# Submarine.net
KiCad netlist of a schematic drawn in EAGLE
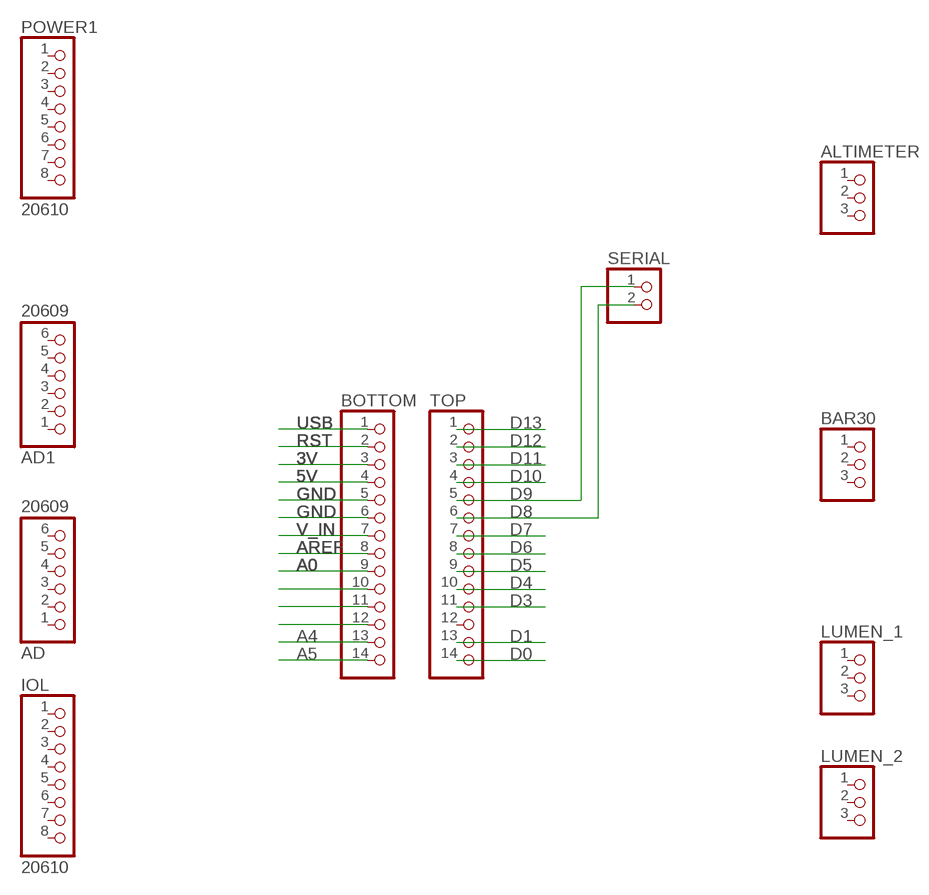
[diagram p0: schematic, sheet 1]

(export (version "E")
  (design (tool "Eeschema 10.0.6"))
  (components
    (comp (ref "AD")
      (value "20609")
      (footprint "eagle-import:1X06_ROUND")
      (libsource (lib "eagle-import") (part "HEADER-1X6ROUND"))
    )
    (comp (ref "AD1")
      (value "20609")
      (footprint "eagle-import:1X06_ROUND")
      (libsource (lib "eagle-import") (part "HEADER-1X6ROUND"))
    )
    (comp (ref "ALTIMETER")
      (value "PINHD-1X3")
      (footprint "eagle-import:1X03")
      (libsource (lib "eagle-import") (part "PINHD-1X3"))
    )
    (comp (ref "BAR30")
      (value "PINHD-1X3")
      (footprint "eagle-import:1X03")
      (libsource (lib "eagle-import") (part "PINHD-1X3"))
    )
    (comp (ref "BOTTOM")
      (value "PINHD-1X14")
      (footprint "eagle-import:1X14")
      (libsource (lib "eagle-import") (part "PINHD-1X14"))
    )
    (comp (ref "IOL")
      (value "20610")
      (footprint "eagle-import:1X08_ROUND")
      (libsource (lib "eagle-import") (part "HEADER-1X8ROUND"))
    )
    (comp (ref "LUMEN_1")
      (value "PINHD-1X3")
      (footprint "eagle-import:1X03")
      (libsource (lib "eagle-import") (part "PINHD-1X3"))
    )
    (comp (ref "LUMEN_2")
      (value "PINHD-1X3")
      (footprint "eagle-import:1X03")
      (libsource (lib "eagle-import") (part "PINHD-1X3"))
    )
    (comp (ref "POWER1")
      (value "20610")
      (footprint "eagle-import:1X08_ROUND_70")
      (libsource (lib "eagle-import") (part "HEADER-1X870MIL"))
    )
    (comp (ref "SERIAL")
      (value "PINHD-1X2")
      (footprint "eagle-import:1X02")
      (libsource (lib "eagle-import") (part "PINHD-1X2"))
    )
    (comp (ref "TOP")
      (value "PINHD-1X14")
      (footprint "eagle-import:1X14")
      (libsource (lib "eagle-import") (part "PINHD-1X14"))
    )
  )
  (nets
    (net (code "1") (name "/3V") (class "Default")
      (node (ref "BOTTOM") (pin "3") (pinfunction "3_3") (pintype "passive"))
    )
    (net (code "2") (name "/5V") (class "Default")
      (node (ref "BOTTOM") (pin "4") (pinfunction "4_4") (pintype "passive"))
    )
    (net (code "3") (name "/A0") (class "Default")
      (node (ref "BOTTOM") (pin "9") (pinfunction "9_9") (pintype "passive"))
    )
    (net (code "4") (name "/A4") (class "Default")
      (node (ref "BOTTOM") (pin "13") (pinfunction "13_13") (pintype "passive"))
    )
    (net (code "5") (name "/A5") (class "Default")
      (node (ref "BOTTOM") (pin "14") (pinfunction "14_14") (pintype "passive"))
    )
    (net (code "6") (name "/AREF") (class "Default")
      (node (ref "BOTTOM") (pin "8") (pinfunction "8_8") (pintype "passive"))
    )
    (net (code "7") (name "/D0") (class "Default")
      (node (ref "TOP") (pin "14") (pinfunction "14_14") (pintype "passive"))
    )
    (net (code "8") (name "/D1") (class "Default")
      (node (ref "TOP") (pin "13") (pinfunction "13_13") (pintype "passive"))
    )
    (net (code "9") (name "/D3") (class "Default")
      (node (ref "TOP") (pin "11") (pinfunction "11_11") (pintype "passive"))
    )
    (net (code "10") (name "/D4") (class "Default")
      (node (ref "TOP") (pin "10") (pinfunction "10_10") (pintype "passive"))
    )
    (net (code "11") (name "/D5") (class "Default")
      (node (ref "TOP") (pin "9") (pinfunction "9_9") (pintype "passive"))
    )
    (net (code "12") (name "/D6") (class "Default")
      (node (ref "TOP") (pin "8") (pinfunction "8_8") (pintype "passive"))
    )
    (net (code "13") (name "/D7") (class "Default")
      (node (ref "TOP") (pin "7") (pinfunction "7_7") (pintype "passive"))
    )
    (net (code "14") (name "/D8") (class "Default")
      (node (ref "SERIAL") (pin "2") (pinfunction "2_2") (pintype "passive"))
      (node (ref "TOP") (pin "6") (pinfunction "6_6") (pintype "passive"))
    )
    (net (code "15") (name "/D9") (class "Default")
      (node (ref "SERIAL") (pin "1") (pinfunction "1_1") (pintype "passive"))
      (node (ref "TOP") (pin "5") (pinfunction "5_5") (pintype "passive"))
    )
    (net (code "16") (name "/D10") (class "Default")
      (node (ref "TOP") (pin "4") (pinfunction "4_4") (pintype "passive"))
    )
    (net (code "17") (name "/D11") (class "Default")
      (node (ref "TOP") (pin "3") (pinfunction "3_3") (pintype "passive"))
    )
    (net (code "18") (name "/D12") (class "Default")
      (node (ref "TOP") (pin "2") (pinfunction "2_2") (pintype "passive"))
    )
    (net (code "19") (name "/D13") (class "Default")
      (node (ref "TOP") (pin "1") (pinfunction "1_1") (pintype "passive"))
    )
    (net (code "20") (name "/GND") (class "Default")
      (node (ref "BOTTOM") (pin "5") (pinfunction "5_5") (pintype "passive"))
      (node (ref "BOTTOM") (pin "6") (pinfunction "6_6") (pintype "passive"))
    )
    (net (code "21") (name "/RST") (class "Default")
      (node (ref "BOTTOM") (pin "2") (pinfunction "2_2") (pintype "passive"))
    )
    (net (code "22") (name "/USB") (class "Default")
      (node (ref "BOTTOM") (pin "1") (pinfunction "1_1") (pintype "passive"))
    )
    (net (code "23") (name "/V_IN") (class "Default")
      (node (ref "BOTTOM") (pin "7") (pinfunction "7_7") (pintype "passive"))
    )
    (net (code "24") (name "unconnected-(AD-Pad1)") (class "Default")
      (node (ref "AD") (pin "1") (pinfunction "1_1") (pintype "passive"))
    )
    (net (code "25") (name "unconnected-(AD-Pad2)") (class "Default")
      (node (ref "AD") (pin "2") (pinfunction "2_2") (pintype "passive"))
    )
    (net (code "26") (name "unconnected-(AD-Pad3)") (class "Default")
      (node (ref "AD") (pin "3") (pinfunction "3_3") (pintype "passive"))
    )
    (net (code "27") (name "unconnected-(AD-Pad4)") (class "Default")
      (node (ref "AD") (pin "4") (pinfunction "4_4") (pintype "passive"))
    )
    (net (code "28") (name "unconnected-(AD-Pad5)") (class "Default")
      (node (ref "AD") (pin "5") (pinfunction "5_5") (pintype "passive"))
    )
    (net (code "29") (name "unconnected-(AD-Pad6)") (class "Default")
      (node (ref "AD") (pin "6") (pinfunction "6_6") (pintype "passive"))
    )
    (net (code "30") (name "unconnected-(AD1-Pad1)") (class "Default")
      (node (ref "AD1") (pin "1") (pinfunction "1_1") (pintype "passive"))
    )
    (net (code "31") (name "unconnected-(AD1-Pad2)") (class "Default")
      (node (ref "AD1") (pin "2") (pinfunction "2_2") (pintype "passive"))
    )
    (net (code "32") (name "unconnected-(AD1-Pad3)") (class "Default")
      (node (ref "AD1") (pin "3") (pinfunction "3_3") (pintype "passive"))
    )
    (net (code "33") (name "unconnected-(AD1-Pad4)") (class "Default")
      (node (ref "AD1") (pin "4") (pinfunction "4_4") (pintype "passive"))
    )
    (net (code "34") (name "unconnected-(AD1-Pad5)") (class "Default")
      (node (ref "AD1") (pin "5") (pinfunction "5_5") (pintype "passive"))
    )
    (net (code "35") (name "unconnected-(AD1-Pad6)") (class "Default")
      (node (ref "AD1") (pin "6") (pinfunction "6_6") (pintype "passive"))
    )
    (net (code "36") (name "unconnected-(ALTIMETER-Pad1)") (class "Default")
      (node (ref "ALTIMETER") (pin "1") (pinfunction "1_1") (pintype "passive"))
    )
    (net (code "37") (name "unconnected-(ALTIMETER-Pad2)") (class "Default")
      (node (ref "ALTIMETER") (pin "2") (pinfunction "2_2") (pintype "passive"))
    )
    (net (code "38") (name "unconnected-(ALTIMETER-Pad3)") (class "Default")
      (node (ref "ALTIMETER") (pin "3") (pinfunction "3_3") (pintype "passive"))
    )
    (net (code "39") (name "unconnected-(BAR30-Pad1)") (class "Default")
      (node (ref "BAR30") (pin "1") (pinfunction "1_1") (pintype "passive"))
    )
    (net (code "40") (name "unconnected-(BAR30-Pad2)") (class "Default")
      (node (ref "BAR30") (pin "2") (pinfunction "2_2") (pintype "passive"))
    )
    (net (code "41") (name "unconnected-(BAR30-Pad3)") (class "Default")
      (node (ref "BAR30") (pin "3") (pinfunction "3_3") (pintype "passive"))
    )
    (net (code "42") (name "unconnected-(BOTTOM-Pad10)") (class "Default")
      (node (ref "BOTTOM") (pin "10") (pinfunction "10_10") (pintype "passive"))
    )
    (net (code "43") (name "unconnected-(BOTTOM-Pad11)") (class "Default")
      (node (ref "BOTTOM") (pin "11") (pinfunction "11_11") (pintype "passive"))
    )
    (net (code "44") (name "unconnected-(BOTTOM-Pad12)") (class "Default")
      (node (ref "BOTTOM") (pin "12") (pinfunction "12_12") (pintype "passive"))
    )
    (net (code "45") (name "unconnected-(IOL-Pad1)") (class "Default")
      (node (ref "IOL") (pin "1") (pinfunction "1_1") (pintype "passive"))
    )
    (net (code "46") (name "unconnected-(IOL-Pad2)") (class "Default")
      (node (ref "IOL") (pin "2") (pinfunction "2_2") (pintype "passive"))
    )
    (net (code "47") (name "unconnected-(IOL-Pad3)") (class "Default")
      (node (ref "IOL") (pin "3") (pinfunction "3_3") (pintype "passive"))
    )
    (net (code "48") (name "unconnected-(IOL-Pad4)") (class "Default")
      (node (ref "IOL") (pin "4") (pinfunction "4_4") (pintype "passive"))
    )
    (net (code "49") (name "unconnected-(IOL-Pad5)") (class "Default")
      (node (ref "IOL") (pin "5") (pinfunction "5_5") (pintype "passive"))
    )
    (net (code "50") (name "unconnected-(IOL-Pad6)") (class "Default")
      (node (ref "IOL") (pin "6") (pinfunction "6_6") (pintype "passive"))
    )
    (net (code "51") (name "unconnected-(IOL-Pad7)") (class "Default")
      (node (ref "IOL") (pin "7") (pinfunction "7_7") (pintype "passive"))
    )
    (net (code "52") (name "unconnected-(IOL-Pad8)") (class "Default")
      (node (ref "IOL") (pin "8") (pinfunction "8_8") (pintype "passive"))
    )
    (net (code "53") (name "unconnected-(LUMEN_1-Pad1)") (class "Default")
      (node (ref "LUMEN_1") (pin "1") (pinfunction "1_1") (pintype "passive"))
    )
    (net (code "54") (name "unconnected-(LUMEN_1-Pad2)") (class "Default")
      (node (ref "LUMEN_1") (pin "2") (pinfunction "2_2") (pintype "passive"))
    )
    (net (code "55") (name "unconnected-(LUMEN_1-Pad3)") (class "Default")
      (node (ref "LUMEN_1") (pin "3") (pinfunction "3_3") (pintype "passive"))
    )
    (net (code "56") (name "unconnected-(LUMEN_2-Pad1)") (class "Default")
      (node (ref "LUMEN_2") (pin "1") (pinfunction "1_1") (pintype "passive"))
    )
    (net (code "57") (name "unconnected-(LUMEN_2-Pad2)") (class "Default")
      (node (ref "LUMEN_2") (pin "2") (pinfunction "2_2") (pintype "passive"))
    )
    (net (code "58") (name "unconnected-(LUMEN_2-Pad3)") (class "Default")
      (node (ref "LUMEN_2") (pin "3") (pinfunction "3_3") (pintype "passive"))
    )
    (net (code "59") (name "unconnected-(POWER1-Pad1)") (class "Default")
      (node (ref "POWER1") (pin "1") (pinfunction "1_1") (pintype "passive"))
    )
    (net (code "60") (name "unconnected-(POWER1-Pad2)") (class "Default")
      (node (ref "POWER1") (pin "2") (pinfunction "2_2") (pintype "passive"))
    )
    (net (code "61") (name "unconnected-(POWER1-Pad3)") (class "Default")
      (node (ref "POWER1") (pin "3") (pinfunction "3_3") (pintype "passive"))
    )
    (net (code "62") (name "unconnected-(POWER1-Pad4)") (class "Default")
      (node (ref "POWER1") (pin "4") (pinfunction "4_4") (pintype "passive"))
    )
    (net (code "63") (name "unconnected-(POWER1-Pad5)") (class "Default")
      (node (ref "POWER1") (pin "5") (pinfunction "5_5") (pintype "passive"))
    )
    (net (code "64") (name "unconnected-(POWER1-Pad6)") (class "Default")
      (node (ref "POWER1") (pin "6") (pinfunction "6_6") (pintype "passive"))
    )
    (net (code "65") (name "unconnected-(POWER1-Pad7)") (class "Default")
      (node (ref "POWER1") (pin "7") (pinfunction "7_7") (pintype "passive"))
    )
    (net (code "66") (name "unconnected-(POWER1-Pad8)") (class "Default")
      (node (ref "POWER1") (pin "8") (pinfunction "8_8") (pintype "passive"))
    )
    (net (code "67") (name "unconnected-(TOP-Pad12)") (class "Default")
      (node (ref "TOP") (pin "12") (pinfunction "12_12") (pintype "passive"))
    )
  )
)
